# SenseGrain-v0_3.net
KiCad netlist of a schematic drawn in EAGLE
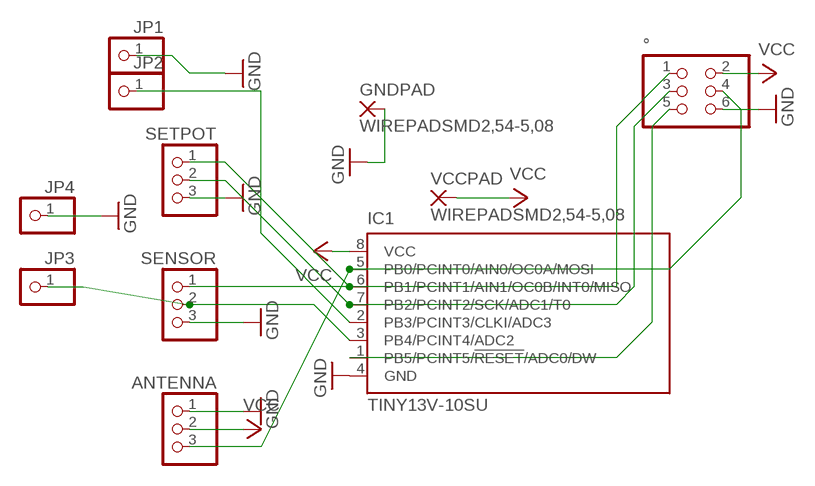
[diagram p0: schematic, sheet 1]

(export (version "E")
  (design (tool "Eeschema 10.0.6"))
  (components
    (comp (ref "ANTENNA")
      (value "PINHD-1X3CB")
      (footprint "eagle-import:1X03-CLEANBIG")
      (libsource (lib "eagle-import") (part "PINHD-1X3CB"))
    )
    (comp (ref "GNDPAD")
      (value "WIREPADSMD2,54-5,08")
      (footprint "eagle-import:SMD2,54-5,08")
      (libsource (lib "eagle-import") (part "WIREPADSMD2,54-5,08"))
    )
    (comp (ref "IC1")
      (value "TINY13V-10SU")
      (footprint "eagle-import:8S2")
      (fields (field (name "MPN") "ATTINY13V-10SU"))
      (libsource (lib "eagle-import") (part "TINY13SUV-10"))
    )
    (comp (ref "JP1")
      (value "PINHD-1X1")
      (footprint "eagle-import:1X01")
      (libsource (lib "eagle-import") (part "PINHD-1X1"))
    )
    (comp (ref "JP2")
      (value "PINHD-1X1")
      (footprint "eagle-import:1X01")
      (libsource (lib "eagle-import") (part "PINHD-1X1"))
    )
    (comp (ref "JP3")
      (value "PINHD-1X1")
      (footprint "eagle-import:1X01")
      (libsource (lib "eagle-import") (part "PINHD-1X1"))
    )
    (comp (ref "JP4")
      (value "PINHD-1X1")
      (footprint "eagle-import:1X01")
      (libsource (lib "eagle-import") (part "PINHD-1X1"))
    )
    (comp (ref "SENSOR")
      (value "PINHD-1X3CB")
      (footprint "eagle-import:1X03-CLEANBIG")
      (libsource (lib "eagle-import") (part "PINHD-1X3CB"))
    )
    (comp (ref "SETPOT")
      (value "PINHD-1X3CB")
      (footprint "eagle-import:1X03-CLEANBIG")
      (libsource (lib "eagle-import") (part "PINHD-1X3CB"))
    )
    (comp (ref "VCCPAD")
      (value "WIREPADSMD2,54-5,08")
      (footprint "eagle-import:SMD2,54-5,08")
      (libsource (lib "eagle-import") (part "WIREPADSMD2,54-5,08"))
    )
    (comp (ref "°")
      (value "PINHD-2X3")
      (footprint "eagle-import:2X03")
      (libsource (lib "eagle-import") (part "PINHD-2X3"))
    )
  )
  (nets
    (net (code "1") (name "GND") (class "Default")
      (node (ref "ANTENNA") (pin "1") (pinfunction "1_1") (pintype "passive"))
      (node (ref "GNDPAD") (pin "1") (pinfunction "P_1") (pintype "passive"))
      (node (ref "IC1") (pin "4") (pinfunction "GND_4") (pintype "power_in"))
      (node (ref "JP1") (pin "1") (pinfunction "1_1") (pintype "passive"))
      (node (ref "JP4") (pin "1") (pinfunction "1_1") (pintype "passive"))
      (node (ref "SENSOR") (pin "3") (pinfunction "3_3") (pintype "passive"))
      (node (ref "SETPOT") (pin "3") (pinfunction "3_3") (pintype "passive"))
      (node (ref "°") (pin "6") (pinfunction "6_6") (pintype "passive"))
    )
    (net (code "2") (name "Net-(IC1-PB0{slash}PCINT0{slash}AIN0{slash}OC0A{slash}MOSI)") (class "Default")
      (node (ref "ANTENNA") (pin "3") (pinfunction "3_3") (pintype "passive"))
      (node (ref "IC1") (pin "5") (pinfunction "PB0/PCINT0/AIN0/OC0A/MOSI_5") (pintype "bidirectional"))
      (node (ref "°") (pin "4") (pinfunction "4_4") (pintype "passive"))
    )
    (net (code "3") (name "Net-(IC1-PB1{slash}PCINT1{slash}AIN1{slash}OC0B{slash}INT0{slash}MISO)") (class "Default")
      (node (ref "IC1") (pin "6") (pinfunction "PB1/PCINT1/AIN1/OC0B/INT0/MISO_6") (pintype "bidirectional"))
      (node (ref "SENSOR") (pin "1") (pinfunction "1_1") (pintype "passive"))
      (node (ref "SETPOT") (pin "1") (pinfunction "1_1") (pintype "passive"))
      (node (ref "°") (pin "1") (pinfunction "1_1") (pintype "passive"))
    )
    (net (code "4") (name "Net-(IC1-PB2{slash}PCINT2{slash}SCK{slash}ADC1{slash}T0)") (class "Default")
      (node (ref "IC1") (pin "7") (pinfunction "PB2/PCINT2/SCK/ADC1/T0_7") (pintype "bidirectional"))
      (node (ref "SETPOT") (pin "2") (pinfunction "2_2") (pintype "passive"))
      (node (ref "°") (pin "3") (pinfunction "3_3") (pintype "passive"))
    )
    (net (code "5") (name "Net-(IC1-PB3{slash}PCINT3{slash}CLKI{slash}ADC3)") (class "Default")
      (node (ref "IC1") (pin "2") (pinfunction "PB3/PCINT3/CLKI/ADC3_2") (pintype "bidirectional"))
      (node (ref "JP2") (pin "1") (pinfunction "1_1") (pintype "passive"))
    )
    (net (code "6") (name "Net-(IC1-PB4{slash}PCINT4{slash}ADC2)") (class "Default")
      (node (ref "IC1") (pin "3") (pinfunction "PB4/PCINT4/ADC2_3") (pintype "bidirectional"))
      (node (ref "JP3") (pin "1") (pinfunction "1_1") (pintype "passive"))
      (node (ref "SENSOR") (pin "2") (pinfunction "2_2") (pintype "passive"))
    )
    (net (code "7") (name "Net-(IC1-PB5{slash}PCINT5{slash}~{RESET}{slash}ADC0{slash}DW)") (class "Default")
      (node (ref "IC1") (pin "1") (pinfunction "PB5/PCINT5/~{RESET}/ADC0/DW_1") (pintype "bidirectional"))
      (node (ref "°") (pin "5") (pinfunction "5_5") (pintype "passive"))
    )
    (net (code "8") (name "VCC") (class "Default")
      (node (ref "ANTENNA") (pin "2") (pinfunction "2_2") (pintype "passive"))
      (node (ref "IC1") (pin "8") (pinfunction "VCC_8") (pintype "power_in"))
      (node (ref "VCCPAD") (pin "1") (pinfunction "P_1") (pintype "passive"))
      (node (ref "°") (pin "2") (pinfunction "2_2") (pintype "passive"))
    )
  )
)
